# EMILL.net
KiCad netlist of a schematic drawn in EAGLE
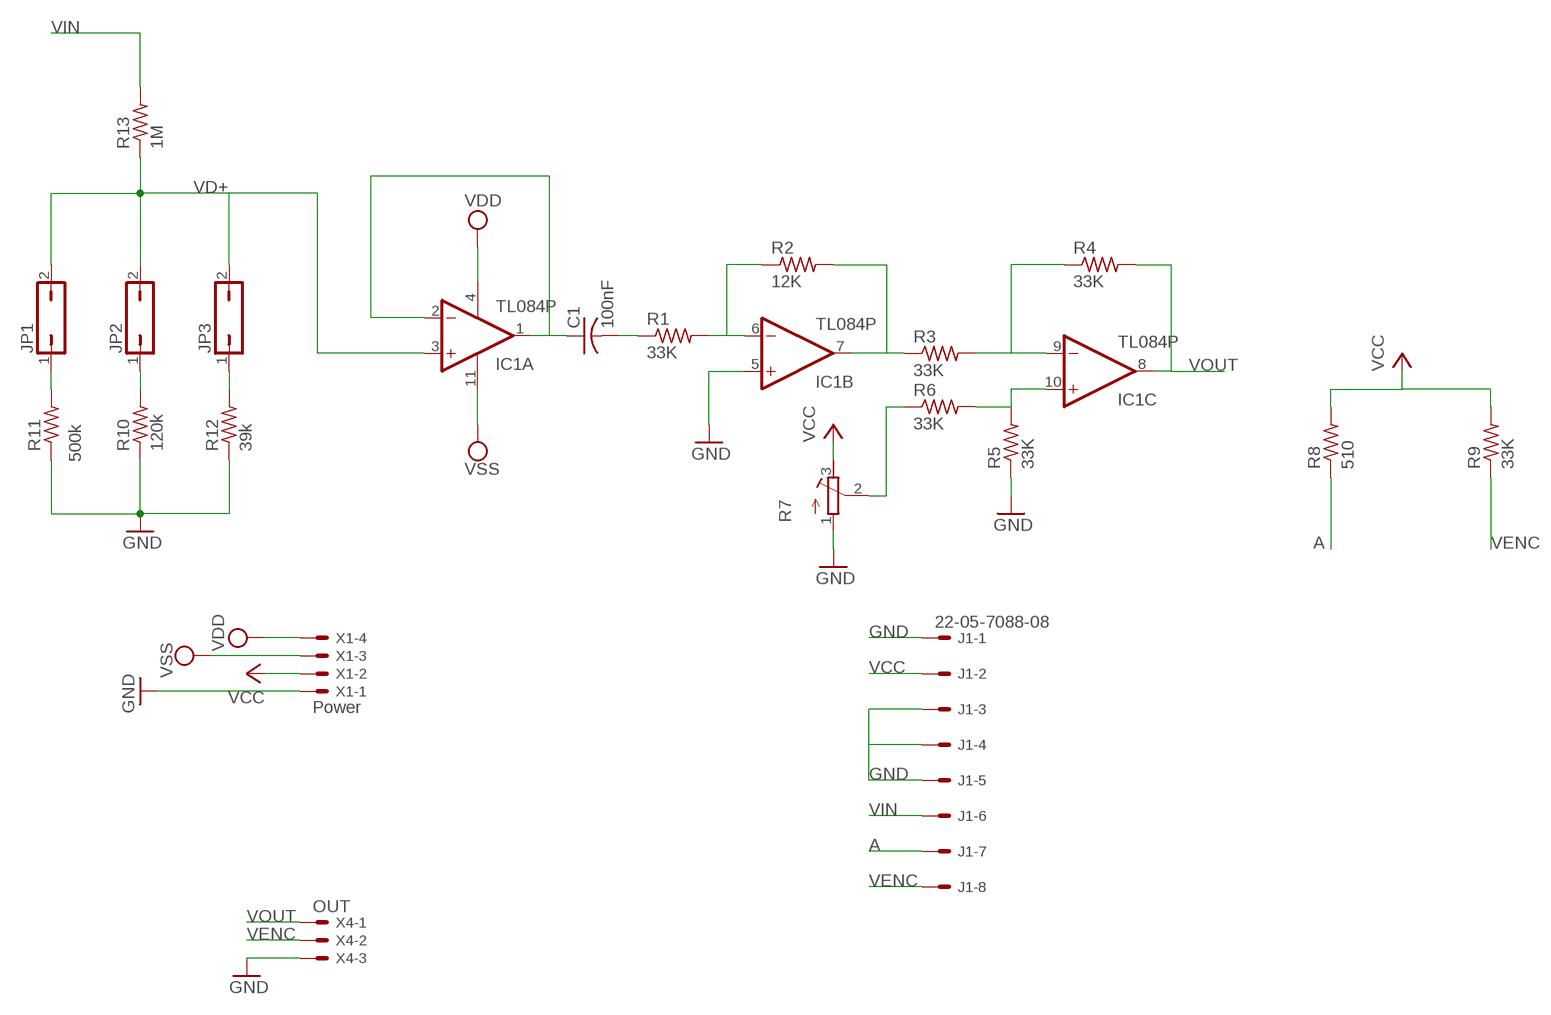
[diagram p0: schematic, sheet 1]

(export (version "E")
  (design (tool "Eeschema 10.0.6"))
  (components
    (comp (ref "C1")
      (value "100nF")
      (footprint "eagle-import:C025-025X050")
      (libsource (lib "eagle-import") (part "C-US025-025X050"))
    )
    (comp (ref "IC1")
      (value "TL084P")
      (footprint "eagle-import:DIL14")
      (libsource (lib "eagle-import") (part "TL084P"))
    )
    (comp (ref "J1")
      (value "22-05-7088-08")
      (footprint "eagle-import:7395-08")
      (fields (field (name "MF") "MOLEX"))
      (libsource (lib "eagle-import") (part "22-?-0805-7088"))
    )
    (comp (ref "JP1")
      (value "JP1Q")
      (footprint "eagle-import:JP1")
      (libsource (lib "eagle-import") (part "JP1Q"))
    )
    (comp (ref "JP2")
      (value "JP1Q")
      (footprint "eagle-import:JP1")
      (libsource (lib "eagle-import") (part "JP1Q"))
    )
    (comp (ref "JP3")
      (value "JP1Q")
      (footprint "eagle-import:JP1")
      (libsource (lib "eagle-import") (part "JP1Q"))
    )
    (comp (ref "R1")
      (value "33K")
      (footprint "eagle-import:0207_10")
      (libsource (lib "eagle-import") (part "R-US_0207/10"))
    )
    (comp (ref "R2")
      (value "12K")
      (footprint "eagle-import:0207_10")
      (libsource (lib "eagle-import") (part "R-US_0207/10"))
    )
    (comp (ref "R3")
      (value "33K")
      (footprint "eagle-import:0207_10")
      (libsource (lib "eagle-import") (part "R-US_0207/10"))
    )
    (comp (ref "R4")
      (value "33K")
      (footprint "eagle-import:0207_10")
      (libsource (lib "eagle-import") (part "R-US_0207/10"))
    )
    (comp (ref "R5")
      (value "33K")
      (footprint "eagle-import:0207_10")
      (libsource (lib "eagle-import") (part "R-US_0207/10"))
    )
    (comp (ref "R6")
      (value "33K")
      (footprint "eagle-import:0207_10")
      (libsource (lib "eagle-import") (part "R-US_0207/10"))
    )
    (comp (ref "R7")
      (value "R-TRIMM64W")
      (footprint "eagle-import:RTRIM64W")
      (libsource (lib "eagle-import") (part "R-TRIMM64W"))
    )
    (comp (ref "R8")
      (value "510")
      (footprint "eagle-import:0207_10")
      (libsource (lib "eagle-import") (part "R-US_0207/10"))
    )
    (comp (ref "R9")
      (value "33K")
      (footprint "eagle-import:0207_10")
      (libsource (lib "eagle-import") (part "R-US_0207/10"))
    )
    (comp (ref "R10")
      (value "120k")
      (footprint "eagle-import:0207_10")
      (libsource (lib "eagle-import") (part "R-US_0207/10"))
    )
    (comp (ref "R11")
      (value "500k")
      (footprint "eagle-import:0207_10")
      (libsource (lib "eagle-import") (part "R-US_0207/10"))
    )
    (comp (ref "R12")
      (value "39k")
      (footprint "eagle-import:0207_10")
      (libsource (lib "eagle-import") (part "R-US_0207/10"))
    )
    (comp (ref "R13")
      (value "1M")
      (footprint "eagle-import:0207_10")
      (libsource (lib "eagle-import") (part "R-US_0207/10"))
    )
    (comp (ref "X1")
      (value "Power")
      (footprint "eagle-import:22-23-2041")
      (fields (field (name "MF") "MOLEX") (field (name "MPN") "22-23-2041"))
      (libsource (lib "eagle-import") (part "22-23-2041"))
    )
    (comp (ref "X4")
      (value "OUT")
      (footprint "eagle-import:22-23-2031")
      (fields (field (name "MF") "MOLEX") (field (name "MPN") "22-23-2031"))
      (libsource (lib "eagle-import") (part "22-23-2031"))
    )
  )
  (nets
    (net (code "1") (name "/A") (class "Default")
      (node (ref "J1") (pin "7") (pinfunction "S_7") (pintype "passive"))
      (node (ref "R8") (pin "1") (pinfunction "1_1") (pintype "passive"))
    )
    (net (code "2") (name "/VD+") (class "Default")
      (node (ref "IC1") (pin "3") (pinfunction "+IN_3") (pintype "input"))
      (node (ref "JP1") (pin "2") (pinfunction "2_2") (pintype "passive"))
      (node (ref "JP2") (pin "2") (pinfunction "2_2") (pintype "passive"))
      (node (ref "JP3") (pin "2") (pinfunction "2_2") (pintype "passive"))
      (node (ref "R13") (pin "1") (pinfunction "1_1") (pintype "passive"))
    )
    (net (code "3") (name "/VENC") (class "Default")
      (node (ref "J1") (pin "8") (pinfunction "S_8") (pintype "passive"))
      (node (ref "R9") (pin "1") (pinfunction "1_1") (pintype "passive"))
      (node (ref "X4") (pin "2") (pinfunction "S_2") (pintype "passive"))
    )
    (net (code "4") (name "/VIN") (class "Default")
      (node (ref "J1") (pin "6") (pinfunction "S_6") (pintype "passive"))
      (node (ref "R13") (pin "2") (pinfunction "2_2") (pintype "passive"))
    )
    (net (code "5") (name "/VOUT") (class "Default")
      (node (ref "IC1") (pin "8") (pinfunction "OUT_8") (pintype "output"))
      (node (ref "R4") (pin "2") (pinfunction "2_2") (pintype "passive"))
      (node (ref "X4") (pin "1") (pinfunction "S_1") (pintype "passive"))
    )
    (net (code "6") (name "GND") (class "Default")
      (node (ref "IC1") (pin "5") (pinfunction "+IN_5") (pintype "input"))
      (node (ref "J1") (pin "1") (pinfunction "S_1") (pintype "passive"))
      (node (ref "J1") (pin "3") (pinfunction "S_3") (pintype "passive"))
      (node (ref "J1") (pin "4") (pinfunction "S_4") (pintype "passive"))
      (node (ref "J1") (pin "5") (pinfunction "S_5") (pintype "passive"))
      (node (ref "R10") (pin "1") (pinfunction "1_1") (pintype "passive"))
      (node (ref "R11") (pin "1") (pinfunction "1_1") (pintype "passive"))
      (node (ref "R12") (pin "1") (pinfunction "1_1") (pintype "passive"))
      (node (ref "R5") (pin "1") (pinfunction "1_1") (pintype "passive"))
      (node (ref "R7") (pin "1") (pinfunction "A_1") (pintype "passive"))
      (node (ref "X1") (pin "1") (pinfunction "S_1") (pintype "passive"))
      (node (ref "X4") (pin "3") (pinfunction "S_3") (pintype "passive"))
    )
    (net (code "7") (name "Net-(C1-Pad2)") (class "Default")
      (node (ref "C1") (pin "2") (pinfunction "2_2") (pintype "passive"))
      (node (ref "R1") (pin "1") (pinfunction "1_1") (pintype "passive"))
    )
    (net (code "8") (name "Net-(IC1A--IN)") (class "Default")
      (node (ref "C1") (pin "1") (pinfunction "1_1") (pintype "passive"))
      (node (ref "IC1") (pin "1") (pinfunction "OUT_1") (pintype "output"))
      (node (ref "IC1") (pin "2") (pinfunction "-IN_2") (pintype "input"))
    )
    (net (code "9") (name "Net-(IC1B--IN)") (class "Default")
      (node (ref "IC1") (pin "6") (pinfunction "-IN_6") (pintype "input"))
      (node (ref "R1") (pin "2") (pinfunction "2_2") (pintype "passive"))
      (node (ref "R2") (pin "1") (pinfunction "1_1") (pintype "passive"))
    )
    (net (code "10") (name "Net-(IC1B-OUT)") (class "Default")
      (node (ref "IC1") (pin "7") (pinfunction "OUT_7") (pintype "output"))
      (node (ref "R2") (pin "2") (pinfunction "2_2") (pintype "passive"))
      (node (ref "R3") (pin "1") (pinfunction "1_1") (pintype "passive"))
    )
    (net (code "11") (name "Net-(IC1C-+IN)") (class "Default")
      (node (ref "IC1") (pin "10") (pinfunction "+IN_10") (pintype "input"))
      (node (ref "R5") (pin "2") (pinfunction "2_2") (pintype "passive"))
      (node (ref "R6") (pin "2") (pinfunction "2_2") (pintype "passive"))
    )
    (net (code "12") (name "Net-(IC1C--IN)") (class "Default")
      (node (ref "IC1") (pin "9") (pinfunction "-IN_9") (pintype "input"))
      (node (ref "R3") (pin "2") (pinfunction "2_2") (pintype "passive"))
      (node (ref "R4") (pin "1") (pinfunction "1_1") (pintype "passive"))
    )
    (net (code "13") (name "Net-(JP1-Pad1)") (class "Default")
      (node (ref "JP1") (pin "1") (pinfunction "1_1") (pintype "passive"))
      (node (ref "R11") (pin "2") (pinfunction "2_2") (pintype "passive"))
    )
    (net (code "14") (name "Net-(JP2-Pad1)") (class "Default")
      (node (ref "JP2") (pin "1") (pinfunction "1_1") (pintype "passive"))
      (node (ref "R10") (pin "2") (pinfunction "2_2") (pintype "passive"))
    )
    (net (code "15") (name "Net-(JP3-Pad1)") (class "Default")
      (node (ref "JP3") (pin "1") (pinfunction "1_1") (pintype "passive"))
      (node (ref "R12") (pin "2") (pinfunction "2_2") (pintype "passive"))
    )
    (net (code "16") (name "Net-(R7-S)") (class "Default")
      (node (ref "R6") (pin "1") (pinfunction "1_1") (pintype "passive"))
      (node (ref "R7") (pin "2") (pinfunction "S_2") (pintype "passive"))
    )
    (net (code "17") (name "VCC") (class "Default")
      (node (ref "J1") (pin "2") (pinfunction "S_2") (pintype "passive"))
      (node (ref "R7") (pin "3") (pinfunction "E_3") (pintype "passive"))
      (node (ref "R8") (pin "2") (pinfunction "2_2") (pintype "passive"))
      (node (ref "R9") (pin "2") (pinfunction "2_2") (pintype "passive"))
      (node (ref "X1") (pin "2") (pinfunction "S_2") (pintype "passive"))
    )
    (net (code "18") (name "VDD") (class "Default")
      (node (ref "IC1") (pin "4") (pinfunction "V+_4") (pintype "power_in"))
      (node (ref "X1") (pin "4") (pinfunction "S_4") (pintype "passive"))
    )
    (net (code "19") (name "VSS") (class "Default")
      (node (ref "IC1") (pin "11") (pinfunction "V-_11") (pintype "power_in"))
      (node (ref "X1") (pin "3") (pinfunction "S_3") (pintype "passive"))
    )
  )
)
